# Sheet1.net
KiCad netlist of a schematic drawn in Altium Designer
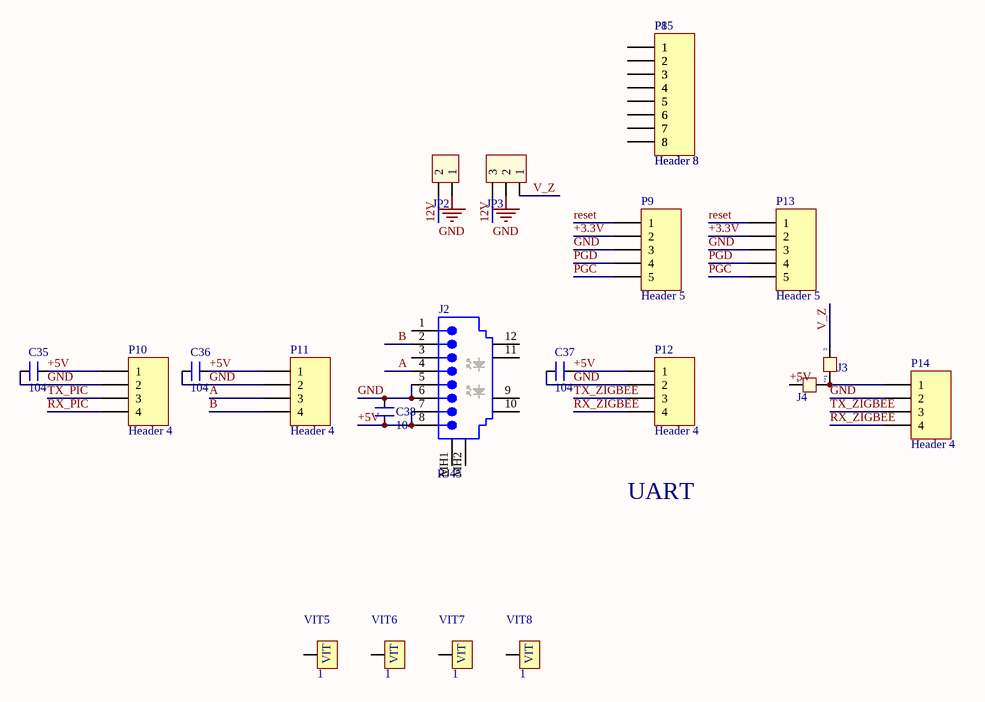
[diagram p0: Sheet1.SchDoc]

(export (version "E")
  (design (tool "Eeschema 10.0.6"))
  (components
    (comp (ref "C35")
      (value "104")
      (footprint "SM-0805")
      (description "Cap SMD")
      (libsource (lib "Luyen_Schematics") (part "CM"))
    )
    (comp (ref "C36")
      (value "104")
      (footprint "SM-0805")
      (description "Cap SMD")
      (libsource (lib "Luyen_Schematics") (part "CM"))
    )
    (comp (ref "C37")
      (value "104")
      (footprint "SM-0805")
      (description "Cap SMD")
      (libsource (lib "Luyen_Schematics") (part "CM"))
    )
    (comp (ref "C38")
      (value "104")
      (footprint "SM-0805")
      (description "Cap SMD")
      (libsource (lib "Luyen_Schematics") (part "CM"))
    )
    (comp (ref "J2")
      (value "RJ45")
      (footprint "RJ45")
      (description "RJ45 Connector, with Leds")
      (libsource (lib "Luyen_Schematics") (part "RJ45"))
    )
    (comp (ref "J3")
      (value "Jumper 2")
      (footprint "SM-0805")
      (libsource (lib "Luyen_Schematics") (part "JP 2"))
    )
    (comp (ref "J4") (value "Jumper 2") (footprint "SM-0805") (libsource (lib "") (part "JP 2_1")))
    (comp (ref "JP2")
      (value "Connector 2")
      (footprint "CON2")
      (libsource (lib "Luyen_Schematics") (part "CON2"))
    )
    (comp (ref "JP3")
      (value "Connector 3")
      (footprint "CON3")
      (libsource (lib "Luyen_Schematics") (part "CON3"))
    )
    (comp (ref "P8")
      (value "Header 8")
      (footprint "con8")
      (description "Header, 8-Pin")
      (fields (field (name "PUBLISHER") "Altium Limited"))
      (libsource (lib "Luyen_Schematics") (part "Header 8"))
    )
    (comp (ref "P9")
      (value "Header 5")
      (footprint "CON5")
      (description "Header, 5-Pin")
      (fields (field (name "PUBLISHER") "Altium Limited"))
      (libsource (lib "Luyen_Schematics") (part "Header 5"))
    )
    (comp (ref "P10")
      (value "Header 4")
      (footprint "CON4")
      (description "Header, 4-Pin")
      (fields (field (name "PUBLISHER") "Altium Limited"))
      (libsource (lib "Luyen_Schematics") (part "Header 4"))
    )
    (comp (ref "P11")
      (value "Header 4")
      (footprint "CON4")
      (description "Header, 4-Pin")
      (fields (field (name "PUBLISHER") "Altium Limited"))
      (libsource (lib "Luyen_Schematics") (part "Header 4"))
    )
    (comp (ref "P12")
      (value "Header 4")
      (footprint "CON4")
      (description "Header, 4-Pin")
      (fields (field (name "PUBLISHER") "Altium Limited"))
      (libsource (lib "Luyen_Schematics") (part "Header 4"))
    )
    (comp (ref "P13")
      (value "Header 5")
      (footprint "CON5")
      (description "Header, 5-Pin")
      (fields (field (name "PUBLISHER") "Altium Limited"))
      (libsource (lib "Luyen_Schematics") (part "Header 5"))
    )
    (comp (ref "P14")
      (value "Header 4")
      (footprint "CON4")
      (description "Header, 4-Pin")
      (fields (field (name "PUBLISHER") "Altium Limited"))
      (libsource (lib "Luyen_Schematics") (part "Header 4"))
    )
    (comp (ref "P15")
      (value "Header 8")
      (footprint "con8")
      (description "Header, 8-Pin")
      (fields (field (name "PUBLISHER") "Altium Limited"))
      (libsource (lib "Luyen_Schematics") (part "Header 8"))
    )
    (comp (ref "VIT5")
      (value "1")
      (footprint "VIT")
      (description "Oc Vit")
      (libsource (lib "Luyen_Schematics") (part "VIT"))
    )
    (comp (ref "VIT6")
      (value "1")
      (footprint "VIT")
      (description "Oc Vit")
      (libsource (lib "Luyen_Schematics") (part "VIT"))
    )
    (comp (ref "VIT7")
      (value "1")
      (footprint "VIT")
      (description "Oc Vit")
      (libsource (lib "Luyen_Schematics") (part "VIT"))
    )
    (comp (ref "VIT8")
      (value "1")
      (footprint "VIT")
      (description "Oc Vit")
      (libsource (lib "Luyen_Schematics") (part "VIT"))
    )
  )
  (nets
    (net (code "1") (name "/+3.3V") (class "Default")
      (node (ref "P13") (pin "2") (pinfunction "2_2") (pintype "passive"))
      (node (ref "P9") (pin "2") (pinfunction "2_2") (pintype "passive"))
    )
    (net (code "2") (name "/+5V") (class "Default")
      (node (ref "C35") (pin "1") (pinfunction "1_1") (pintype "passive"))
      (node (ref "C36") (pin "1") (pinfunction "1_1") (pintype "passive"))
      (node (ref "C37") (pin "2") (pinfunction "2_2") (pintype "passive"))
      (node (ref "C38") (pin "2") (pinfunction "2_2") (pintype "passive"))
      (node (ref "J2") (pin "7") (pinfunction "7_7") (pintype "passive"))
      (node (ref "J2") (pin "8") (pinfunction "8_8") (pintype "passive"))
      (node (ref "J4") (pin "1") (pinfunction "1_1") (pintype "passive"))
      (node (ref "P10") (pin "1") (pinfunction "1_1") (pintype "passive"))
      (node (ref "P11") (pin "1") (pinfunction "1_1") (pintype "passive"))
      (node (ref "P12") (pin "1") (pinfunction "1_1") (pintype "passive"))
    )
    (net (code "3") (name "/12V") (class "Default")
      (node (ref "JP2") (pin "2") (pinfunction "2_2") (pintype "passive"))
      (node (ref "JP3") (pin "3") (pinfunction "3_3") (pintype "passive"))
    )
    (net (code "4") (name "/A") (class "Default")
      (node (ref "J2") (pin "4") (pinfunction "4_4") (pintype "passive"))
      (node (ref "P11") (pin "3") (pinfunction "3_3") (pintype "passive"))
    )
    (net (code "5") (name "/B") (class "Default")
      (node (ref "J2") (pin "2") (pinfunction "2_2") (pintype "passive"))
      (node (ref "P11") (pin "4") (pinfunction "4_4") (pintype "passive"))
    )
    (net (code "6") (name "/PGC") (class "Default")
      (node (ref "P13") (pin "5") (pinfunction "5_5") (pintype "passive"))
      (node (ref "P9") (pin "5") (pinfunction "5_5") (pintype "passive"))
    )
    (net (code "7") (name "/PGD") (class "Default")
      (node (ref "P13") (pin "4") (pinfunction "4_4") (pintype "passive"))
      (node (ref "P9") (pin "4") (pinfunction "4_4") (pintype "passive"))
    )
    (net (code "8") (name "/RX_PIC") (class "Default")
      (node (ref "P10") (pin "4") (pinfunction "4_4") (pintype "passive"))
    )
    (net (code "9") (name "/RX_ZIGBEE") (class "Default")
      (node (ref "P12") (pin "4") (pinfunction "4_4") (pintype "passive"))
      (node (ref "P14") (pin "4") (pinfunction "4_4") (pintype "passive"))
    )
    (net (code "10") (name "/TX_PIC") (class "Default")
      (node (ref "P10") (pin "3") (pinfunction "3_3") (pintype "passive"))
    )
    (net (code "11") (name "/TX_ZIGBEE") (class "Default")
      (node (ref "P12") (pin "3") (pinfunction "3_3") (pintype "passive"))
      (node (ref "P14") (pin "3") (pinfunction "3_3") (pintype "passive"))
    )
    (net (code "12") (name "/V_Z") (class "Default")
      (node (ref "J3") (pin "2") (pinfunction "2_2") (pintype "passive"))
      (node (ref "JP3") (pin "1") (pinfunction "1_1") (pintype "passive"))
    )
    (net (code "13") (name "/reset") (class "Default")
      (node (ref "P13") (pin "1") (pinfunction "1_1") (pintype "passive"))
      (node (ref "P9") (pin "1") (pinfunction "1_1") (pintype "passive"))
    )
    (net (code "14") (name "GND") (class "Default")
      (node (ref "C35") (pin "2") (pinfunction "2_2") (pintype "passive"))
      (node (ref "C36") (pin "2") (pinfunction "2_2") (pintype "passive"))
      (node (ref "C37") (pin "1") (pinfunction "1_1") (pintype "passive"))
      (node (ref "C38") (pin "1") (pinfunction "1_1") (pintype "passive"))
      (node (ref "J2") (pin "5") (pinfunction "5_5") (pintype "passive"))
      (node (ref "J2") (pin "6") (pinfunction "6_6") (pintype "passive"))
      (node (ref "JP2") (pin "1") (pinfunction "1_1") (pintype "passive"))
      (node (ref "JP3") (pin "2") (pinfunction "2_2") (pintype "passive"))
      (node (ref "P10") (pin "2") (pinfunction "2_2") (pintype "passive"))
      (node (ref "P11") (pin "2") (pinfunction "2_2") (pintype "passive"))
      (node (ref "P12") (pin "2") (pinfunction "2_2") (pintype "passive"))
      (node (ref "P13") (pin "3") (pinfunction "3_3") (pintype "passive"))
      (node (ref "P14") (pin "2") (pinfunction "2_2") (pintype "passive"))
      (node (ref "P9") (pin "3") (pinfunction "3_3") (pintype "passive"))
    )
    (net (code "15") (name "Net-(J3-Pad1)") (class "Default")
      (node (ref "J3") (pin "1") (pinfunction "1_1") (pintype "passive"))
      (node (ref "J4") (pin "2") (pinfunction "2_2") (pintype "passive"))
      (node (ref "P14") (pin "1") (pinfunction "1_1") (pintype "passive"))
    )
    (net (code "16") (name "Net-(P15-Pad1)") (class "Default")
      (node (ref "P15") (pin "1") (pinfunction "1_1") (pintype "passive"))
      (node (ref "P8") (pin "1") (pinfunction "1_1") (pintype "passive"))
    )
    (net (code "17") (name "Net-(P15-Pad2)") (class "Default")
      (node (ref "P15") (pin "2") (pinfunction "2_2") (pintype "passive"))
      (node (ref "P8") (pin "2") (pinfunction "2_2") (pintype "passive"))
    )
    (net (code "18") (name "Net-(P15-Pad3)") (class "Default")
      (node (ref "P15") (pin "3") (pinfunction "3_3") (pintype "passive"))
      (node (ref "P8") (pin "3") (pinfunction "3_3") (pintype "passive"))
    )
    (net (code "19") (name "Net-(P15-Pad4)") (class "Default")
      (node (ref "P15") (pin "4") (pinfunction "4_4") (pintype "passive"))
      (node (ref "P8") (pin "4") (pinfunction "4_4") (pintype "passive"))
    )
    (net (code "20") (name "Net-(P15-Pad5)") (class "Default")
      (node (ref "P15") (pin "5") (pinfunction "5_5") (pintype "passive"))
      (node (ref "P8") (pin "5") (pinfunction "5_5") (pintype "passive"))
    )
    (net (code "21") (name "Net-(P15-Pad6)") (class "Default")
      (node (ref "P15") (pin "6") (pinfunction "6_6") (pintype "passive"))
      (node (ref "P8") (pin "6") (pinfunction "6_6") (pintype "passive"))
    )
    (net (code "22") (name "Net-(P15-Pad7)") (class "Default")
      (node (ref "P15") (pin "7") (pinfunction "7_7") (pintype "passive"))
      (node (ref "P8") (pin "7") (pinfunction "7_7") (pintype "passive"))
    )
    (net (code "23") (name "Net-(P15-Pad8)") (class "Default")
      (node (ref "P15") (pin "8") (pinfunction "8_8") (pintype "passive"))
      (node (ref "P8") (pin "8") (pinfunction "8_8") (pintype "passive"))
    )
    (net (code "24") (name "unconnected-(J2-Pad1)") (class "Default")
      (node (ref "J2") (pin "1") (pinfunction "1_1") (pintype "passive"))
    )
    (net (code "25") (name "unconnected-(J2-Pad3)") (class "Default")
      (node (ref "J2") (pin "3") (pinfunction "3_3") (pintype "passive"))
    )
    (net (code "26") (name "unconnected-(J2-Pad9)") (class "Default")
      (node (ref "J2") (pin "9") (pinfunction "9_9") (pintype "passive"))
    )
    (net (code "27") (name "unconnected-(J2-Pad10)") (class "Default")
      (node (ref "J2") (pin "10") (pinfunction "10_10") (pintype "passive"))
    )
    (net (code "28") (name "unconnected-(J2-Pad11)") (class "Default")
      (node (ref "J2") (pin "11") (pinfunction "11_11") (pintype "passive"))
    )
    (net (code "29") (name "unconnected-(J2-Pad12)") (class "Default")
      (node (ref "J2") (pin "12") (pinfunction "12_12") (pintype "passive"))
    )
    (net (code "30") (name "unconnected-(J2-Shield-PadMH1)") (class "Default")
      (node (ref "J2") (pin "MH1") (pinfunction "Shield_MH1") (pintype "passive"))
    )
    (net (code "31") (name "unconnected-(J2-Shield-PadMH2)") (class "Default")
      (node (ref "J2") (pin "MH2") (pinfunction "Shield_MH2") (pintype "passive"))
    )
    (net (code "32") (name "unconnected-(VIT5-1-PadVIT1)") (class "Default")
      (node (ref "VIT5") (pin "VIT1") (pinfunction "1_VIT1") (pintype "passive"))
    )
    (net (code "33") (name "unconnected-(VIT6-1-PadVIT1)") (class "Default")
      (node (ref "VIT6") (pin "VIT1") (pinfunction "1_VIT1") (pintype "passive"))
    )
    (net (code "34") (name "unconnected-(VIT7-1-PadVIT1)") (class "Default")
      (node (ref "VIT7") (pin "VIT1") (pinfunction "1_VIT1") (pintype "passive"))
    )
    (net (code "35") (name "unconnected-(VIT8-1-PadVIT1)") (class "Default")
      (node (ref "VIT8") (pin "VIT1") (pinfunction "1_VIT1") (pintype "passive"))
    )
  )
)
